# L298N_MOTOR_S_R_C.net
KiCad netlist of a schematic drawn in EAGLE
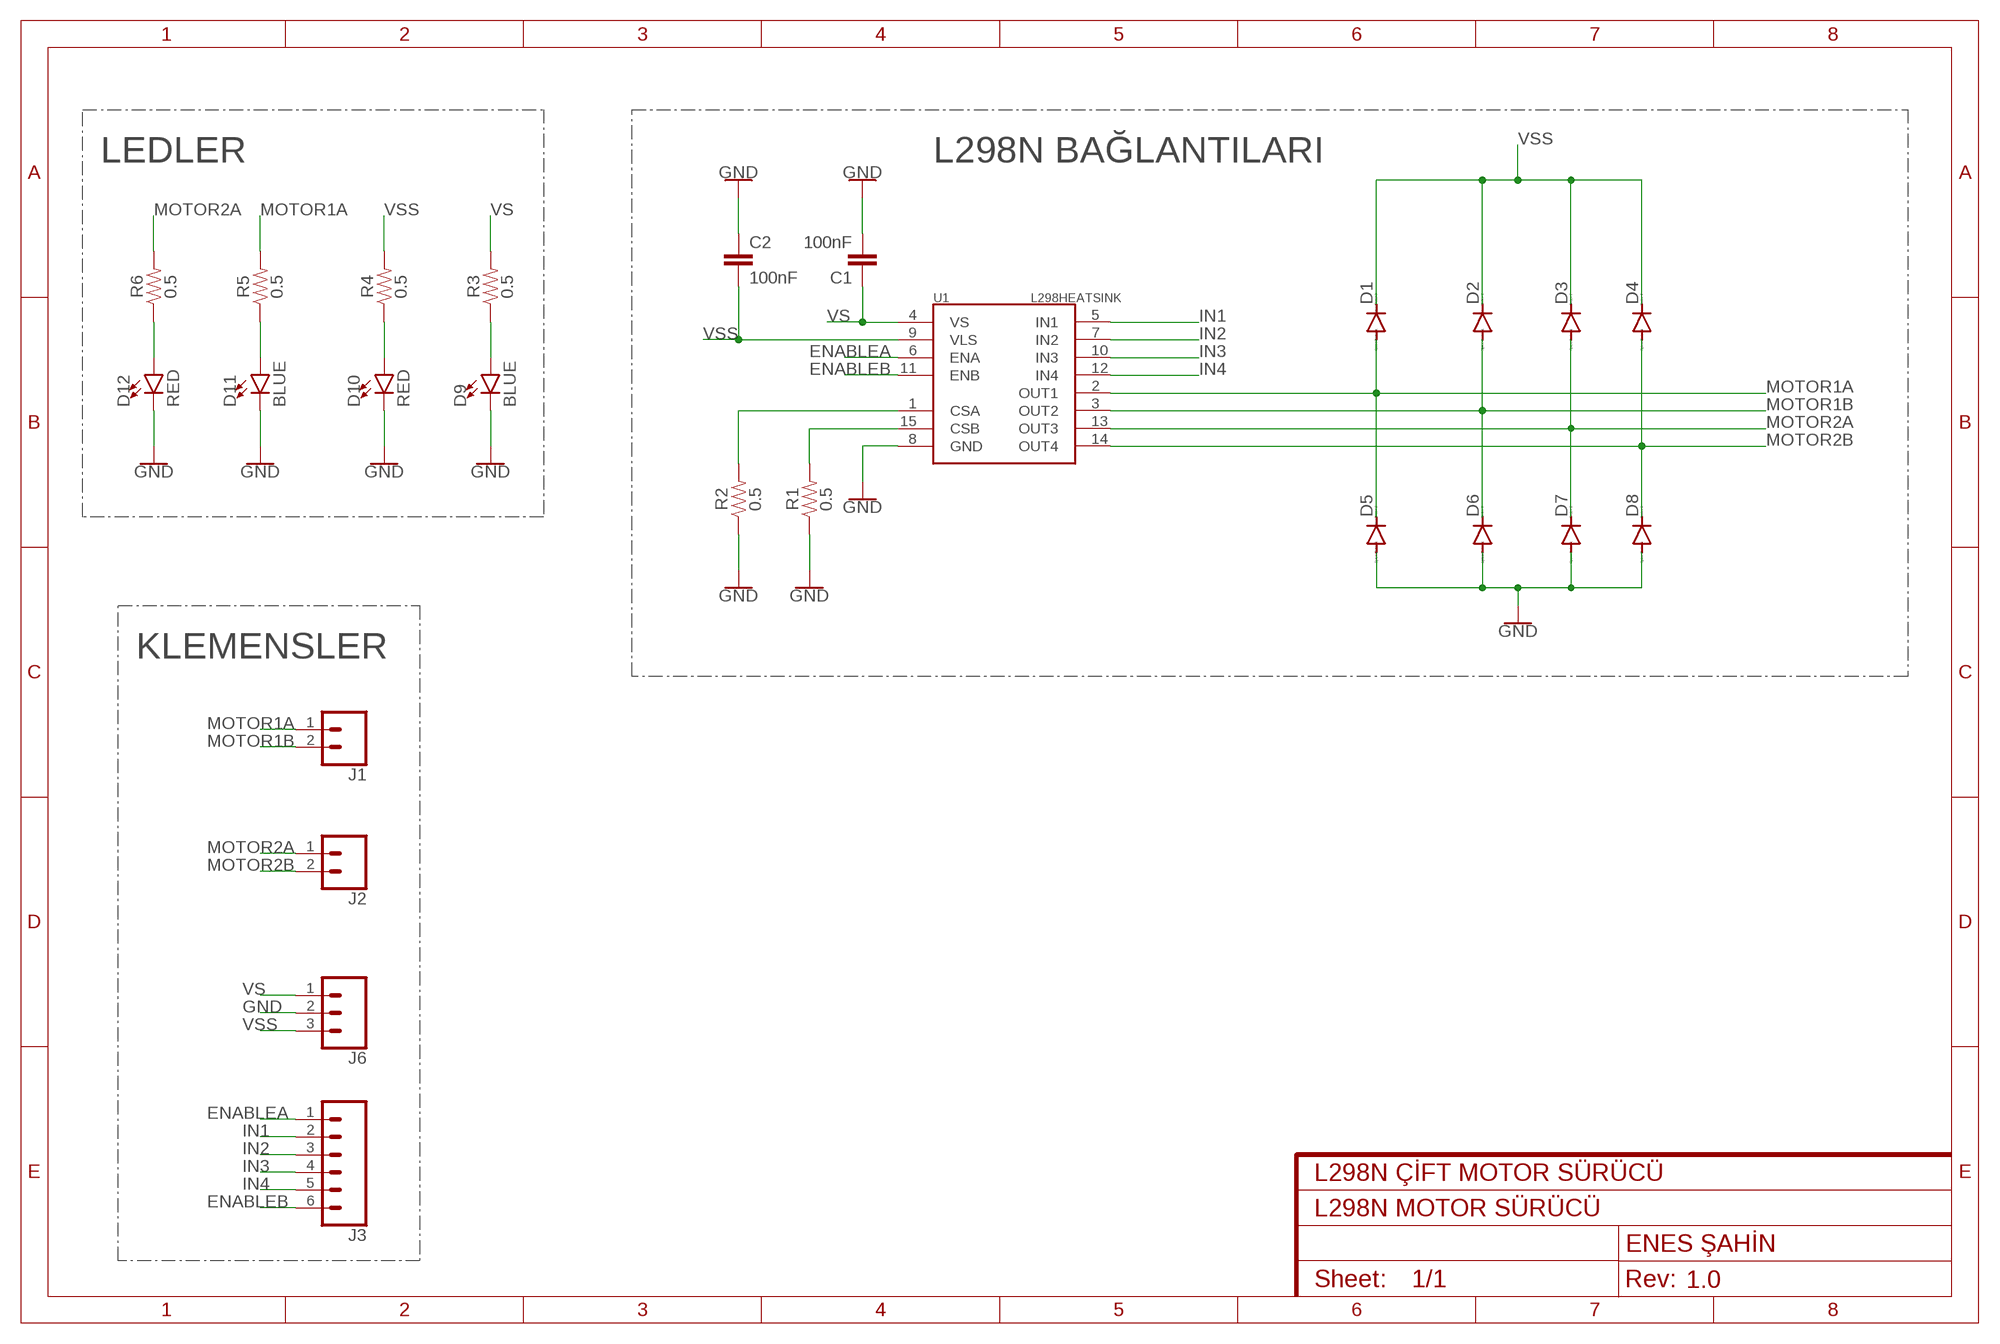
[diagram p0: schematic, sheet 1]

(export (version "E")
  (design (tool "Eeschema 10.0.6"))
  (components
    (comp (ref "C1")
      (value "100nF")
      (footprint "eagle-import:0603")
      (libsource (lib "eagle-import") (part "10NF-0603-50V-10%"))
    )
    (comp (ref "C2")
      (value "100nF")
      (footprint "eagle-import:0603")
      (libsource (lib "eagle-import") (part "10NF-0603-50V-10%"))
    )
    (comp (ref "D1")
      (value "CGRM4007-G")
      (footprint "eagle-import:SOD-123_MINI-SMA")
      (libsource (lib "eagle-import") (part "CGRM400-G7"))
    )
    (comp (ref "D2")
      (value "CGRM4007-G")
      (footprint "eagle-import:SOD-123_MINI-SMA")
      (libsource (lib "eagle-import") (part "CGRM400-G7"))
    )
    (comp (ref "D3")
      (value "CGRM4007-G")
      (footprint "eagle-import:SOD-123_MINI-SMA")
      (libsource (lib "eagle-import") (part "CGRM400-G7"))
    )
    (comp (ref "D4")
      (value "CGRM4007-G")
      (footprint "eagle-import:SOD-123_MINI-SMA")
      (libsource (lib "eagle-import") (part "CGRM400-G7"))
    )
    (comp (ref "D5")
      (value "CGRM4007-G")
      (footprint "eagle-import:SOD-123_MINI-SMA")
      (libsource (lib "eagle-import") (part "CGRM400-G7"))
    )
    (comp (ref "D6")
      (value "CGRM4007-G")
      (footprint "eagle-import:SOD-123_MINI-SMA")
      (libsource (lib "eagle-import") (part "CGRM400-G7"))
    )
    (comp (ref "D7")
      (value "CGRM4007-G")
      (footprint "eagle-import:SOD-123_MINI-SMA")
      (libsource (lib "eagle-import") (part "CGRM400-G7"))
    )
    (comp (ref "D8")
      (value "CGRM4007-G")
      (footprint "eagle-import:SOD-123_MINI-SMA")
      (libsource (lib "eagle-import") (part "CGRM400-G7"))
    )
    (comp (ref "D9")
      (value "BLUE")
      (footprint "eagle-import:LED-0603")
      (libsource (lib "eagle-import") (part "LED-BLUE0603"))
    )
    (comp (ref "D10")
      (value "RED")
      (footprint "eagle-import:LED-0603")
      (libsource (lib "eagle-import") (part "LED-RED0603"))
    )
    (comp (ref "D11")
      (value "BLUE")
      (footprint "eagle-import:LED-0603")
      (libsource (lib "eagle-import") (part "LED-BLUE0603"))
    )
    (comp (ref "D12")
      (value "RED")
      (footprint "eagle-import:LED-0603")
      (libsource (lib "eagle-import") (part "LED-RED0603"))
    )
    (comp (ref "J1")
      (value "CONN_02")
      (footprint "eagle-import:1X02")
      (libsource (lib "eagle-import") (part "CONN_02"))
    )
    (comp (ref "J2")
      (value "CONN_02")
      (footprint "eagle-import:1X02")
      (libsource (lib "eagle-import") (part "CONN_02"))
    )
    (comp (ref "J3")
      (value "CONN_06SILK_FEMALE_PTH")
      (footprint "eagle-import:1X06")
      (libsource (lib "eagle-import") (part "CONN_06SILK_FEMALE_PTH"))
    )
    (comp (ref "J6")
      (value "CONN_03")
      (footprint "eagle-import:1X03")
      (libsource (lib "eagle-import") (part "CONN_03"))
    )
    (comp (ref "R1")
      (value "0.5")
      (footprint "eagle-import:0603")
      (libsource (lib "eagle-import") (part "0.05OHM-0603-1/5W-1%"))
    )
    (comp (ref "R2")
      (value "0.5")
      (footprint "eagle-import:0603")
      (libsource (lib "eagle-import") (part "0.05OHM-0603-1/5W-1%"))
    )
    (comp (ref "R3")
      (value "0.5")
      (footprint "eagle-import:0603")
      (libsource (lib "eagle-import") (part "0.05OHM-0603-1/5W-1%"))
    )
    (comp (ref "R4")
      (value "0.5")
      (footprint "eagle-import:0603")
      (libsource (lib "eagle-import") (part "0.05OHM-0603-1/5W-1%"))
    )
    (comp (ref "R5")
      (value "0.5")
      (footprint "eagle-import:0603")
      (libsource (lib "eagle-import") (part "0.05OHM-0603-1/5W-1%"))
    )
    (comp (ref "R6")
      (value "0.5")
      (footprint "eagle-import:0603")
      (libsource (lib "eagle-import") (part "0.05OHM-0603-1/5W-1%"))
    )
    (comp (ref "U1")
      (value "L298HEATSINK")
      (footprint "eagle-import:MULTIWATT15_6400BGHEATSINK")
      (libsource (lib "eagle-import") (part "L298HEATSINK"))
    )
  )
  (nets
    (net (code "1") (name "/ENABLEA") (class "Default")
      (node (ref "J3") (pin "1") (pinfunction "1_1") (pintype "passive"))
      (node (ref "U1") (pin "6") (pinfunction "ENA_6") (pintype "bidirectional"))
    )
    (net (code "2") (name "/ENABLEB") (class "Default")
      (node (ref "J3") (pin "6") (pinfunction "6_6") (pintype "passive"))
      (node (ref "U1") (pin "11") (pinfunction "ENB_11") (pintype "bidirectional"))
    )
    (net (code "3") (name "/IN1") (class "Default")
      (node (ref "J3") (pin "2") (pinfunction "2_2") (pintype "passive"))
      (node (ref "U1") (pin "5") (pinfunction "IN1_5") (pintype "bidirectional"))
    )
    (net (code "4") (name "/IN2") (class "Default")
      (node (ref "J3") (pin "3") (pinfunction "3_3") (pintype "passive"))
      (node (ref "U1") (pin "7") (pinfunction "IN2_7") (pintype "bidirectional"))
    )
    (net (code "5") (name "/IN3") (class "Default")
      (node (ref "J3") (pin "4") (pinfunction "4_4") (pintype "passive"))
      (node (ref "U1") (pin "10") (pinfunction "IN3_10") (pintype "bidirectional"))
    )
    (net (code "6") (name "/IN4") (class "Default")
      (node (ref "J3") (pin "5") (pinfunction "5_5") (pintype "passive"))
      (node (ref "U1") (pin "12") (pinfunction "IN4_12") (pintype "bidirectional"))
    )
    (net (code "7") (name "/MOTOR1A") (class "Default")
      (node (ref "D1") (pin "A") (pinfunction "A_A") (pintype "passive"))
      (node (ref "D5") (pin "C") (pinfunction "C_C") (pintype "passive"))
      (node (ref "J1") (pin "1") (pinfunction "1_1") (pintype "passive"))
      (node (ref "R5") (pin "2") (pinfunction "2_2") (pintype "passive"))
      (node (ref "U1") (pin "2") (pinfunction "OUT1_2") (pintype "bidirectional"))
    )
    (net (code "8") (name "/MOTOR1B") (class "Default")
      (node (ref "D2") (pin "A") (pinfunction "A_A") (pintype "passive"))
      (node (ref "D6") (pin "C") (pinfunction "C_C") (pintype "passive"))
      (node (ref "J1") (pin "2") (pinfunction "2_2") (pintype "passive"))
      (node (ref "U1") (pin "3") (pinfunction "OUT2_3") (pintype "bidirectional"))
    )
    (net (code "9") (name "/MOTOR2A") (class "Default")
      (node (ref "D3") (pin "A") (pinfunction "A_A") (pintype "passive"))
      (node (ref "D7") (pin "C") (pinfunction "C_C") (pintype "passive"))
      (node (ref "J2") (pin "1") (pinfunction "1_1") (pintype "passive"))
      (node (ref "R6") (pin "2") (pinfunction "2_2") (pintype "passive"))
      (node (ref "U1") (pin "13") (pinfunction "OUT3_13") (pintype "bidirectional"))
    )
    (net (code "10") (name "/MOTOR2B") (class "Default")
      (node (ref "D4") (pin "A") (pinfunction "A_A") (pintype "passive"))
      (node (ref "D8") (pin "C") (pinfunction "C_C") (pintype "passive"))
      (node (ref "J2") (pin "2") (pinfunction "2_2") (pintype "passive"))
      (node (ref "U1") (pin "14") (pinfunction "OUT4_14") (pintype "bidirectional"))
    )
    (net (code "11") (name "/VS") (class "Default")
      (node (ref "C1") (pin "1") (pinfunction "1_1") (pintype "passive"))
      (node (ref "J6") (pin "1") (pinfunction "1_1") (pintype "passive"))
      (node (ref "R3") (pin "2") (pinfunction "2_2") (pintype "passive"))
      (node (ref "U1") (pin "4") (pinfunction "VS_4") (pintype "bidirectional"))
    )
    (net (code "12") (name "/VSS") (class "Default")
      (node (ref "C2") (pin "2") (pinfunction "2_2") (pintype "passive"))
      (node (ref "D1") (pin "C") (pinfunction "C_C") (pintype "passive"))
      (node (ref "D2") (pin "C") (pinfunction "C_C") (pintype "passive"))
      (node (ref "D3") (pin "C") (pinfunction "C_C") (pintype "passive"))
      (node (ref "D4") (pin "C") (pinfunction "C_C") (pintype "passive"))
      (node (ref "J6") (pin "3") (pinfunction "3_3") (pintype "passive"))
      (node (ref "R4") (pin "2") (pinfunction "2_2") (pintype "passive"))
      (node (ref "U1") (pin "9") (pinfunction "VLS_9") (pintype "bidirectional"))
    )
    (net (code "13") (name "GND") (class "Default")
      (node (ref "C1") (pin "2") (pinfunction "2_2") (pintype "passive"))
      (node (ref "C2") (pin "1") (pinfunction "1_1") (pintype "passive"))
      (node (ref "D10") (pin "C") (pinfunction "C_C") (pintype "passive"))
      (node (ref "D11") (pin "C") (pinfunction "C_C") (pintype "passive"))
      (node (ref "D12") (pin "C") (pinfunction "C_C") (pintype "passive"))
      (node (ref "D5") (pin "A") (pinfunction "A_A") (pintype "passive"))
      (node (ref "D6") (pin "A") (pinfunction "A_A") (pintype "passive"))
      (node (ref "D7") (pin "A") (pinfunction "A_A") (pintype "passive"))
      (node (ref "D8") (pin "A") (pinfunction "A_A") (pintype "passive"))
      (node (ref "D9") (pin "C") (pinfunction "C_C") (pintype "passive"))
      (node (ref "J6") (pin "2") (pinfunction "2_2") (pintype "passive"))
      (node (ref "R1") (pin "1") (pinfunction "1_1") (pintype "passive"))
      (node (ref "R2") (pin "1") (pinfunction "1_1") (pintype "passive"))
      (node (ref "U1") (pin "8") (pinfunction "GND_8") (pintype "bidirectional"))
    )
    (net (code "14") (name "Net-(D9-PadA)") (class "Default")
      (node (ref "D9") (pin "A") (pinfunction "A_A") (pintype "passive"))
      (node (ref "R3") (pin "1") (pinfunction "1_1") (pintype "passive"))
    )
    (net (code "15") (name "Net-(D10-PadA)") (class "Default")
      (node (ref "D10") (pin "A") (pinfunction "A_A") (pintype "passive"))
      (node (ref "R4") (pin "1") (pinfunction "1_1") (pintype "passive"))
    )
    (net (code "16") (name "Net-(D11-PadA)") (class "Default")
      (node (ref "D11") (pin "A") (pinfunction "A_A") (pintype "passive"))
      (node (ref "R5") (pin "1") (pinfunction "1_1") (pintype "passive"))
    )
    (net (code "17") (name "Net-(D12-PadA)") (class "Default")
      (node (ref "D12") (pin "A") (pinfunction "A_A") (pintype "passive"))
      (node (ref "R6") (pin "1") (pinfunction "1_1") (pintype "passive"))
    )
    (net (code "18") (name "Net-(U1-CSA)") (class "Default")
      (node (ref "R2") (pin "2") (pinfunction "2_2") (pintype "passive"))
      (node (ref "U1") (pin "1") (pinfunction "CSA_1") (pintype "bidirectional"))
    )
    (net (code "19") (name "Net-(U1-CSB)") (class "Default")
      (node (ref "R1") (pin "2") (pinfunction "2_2") (pintype "passive"))
      (node (ref "U1") (pin "15") (pinfunction "CSB_15") (pintype "bidirectional"))
    )
  )
)
